# smart_irrigation.net
KiCad netlist of a schematic drawn in EAGLE
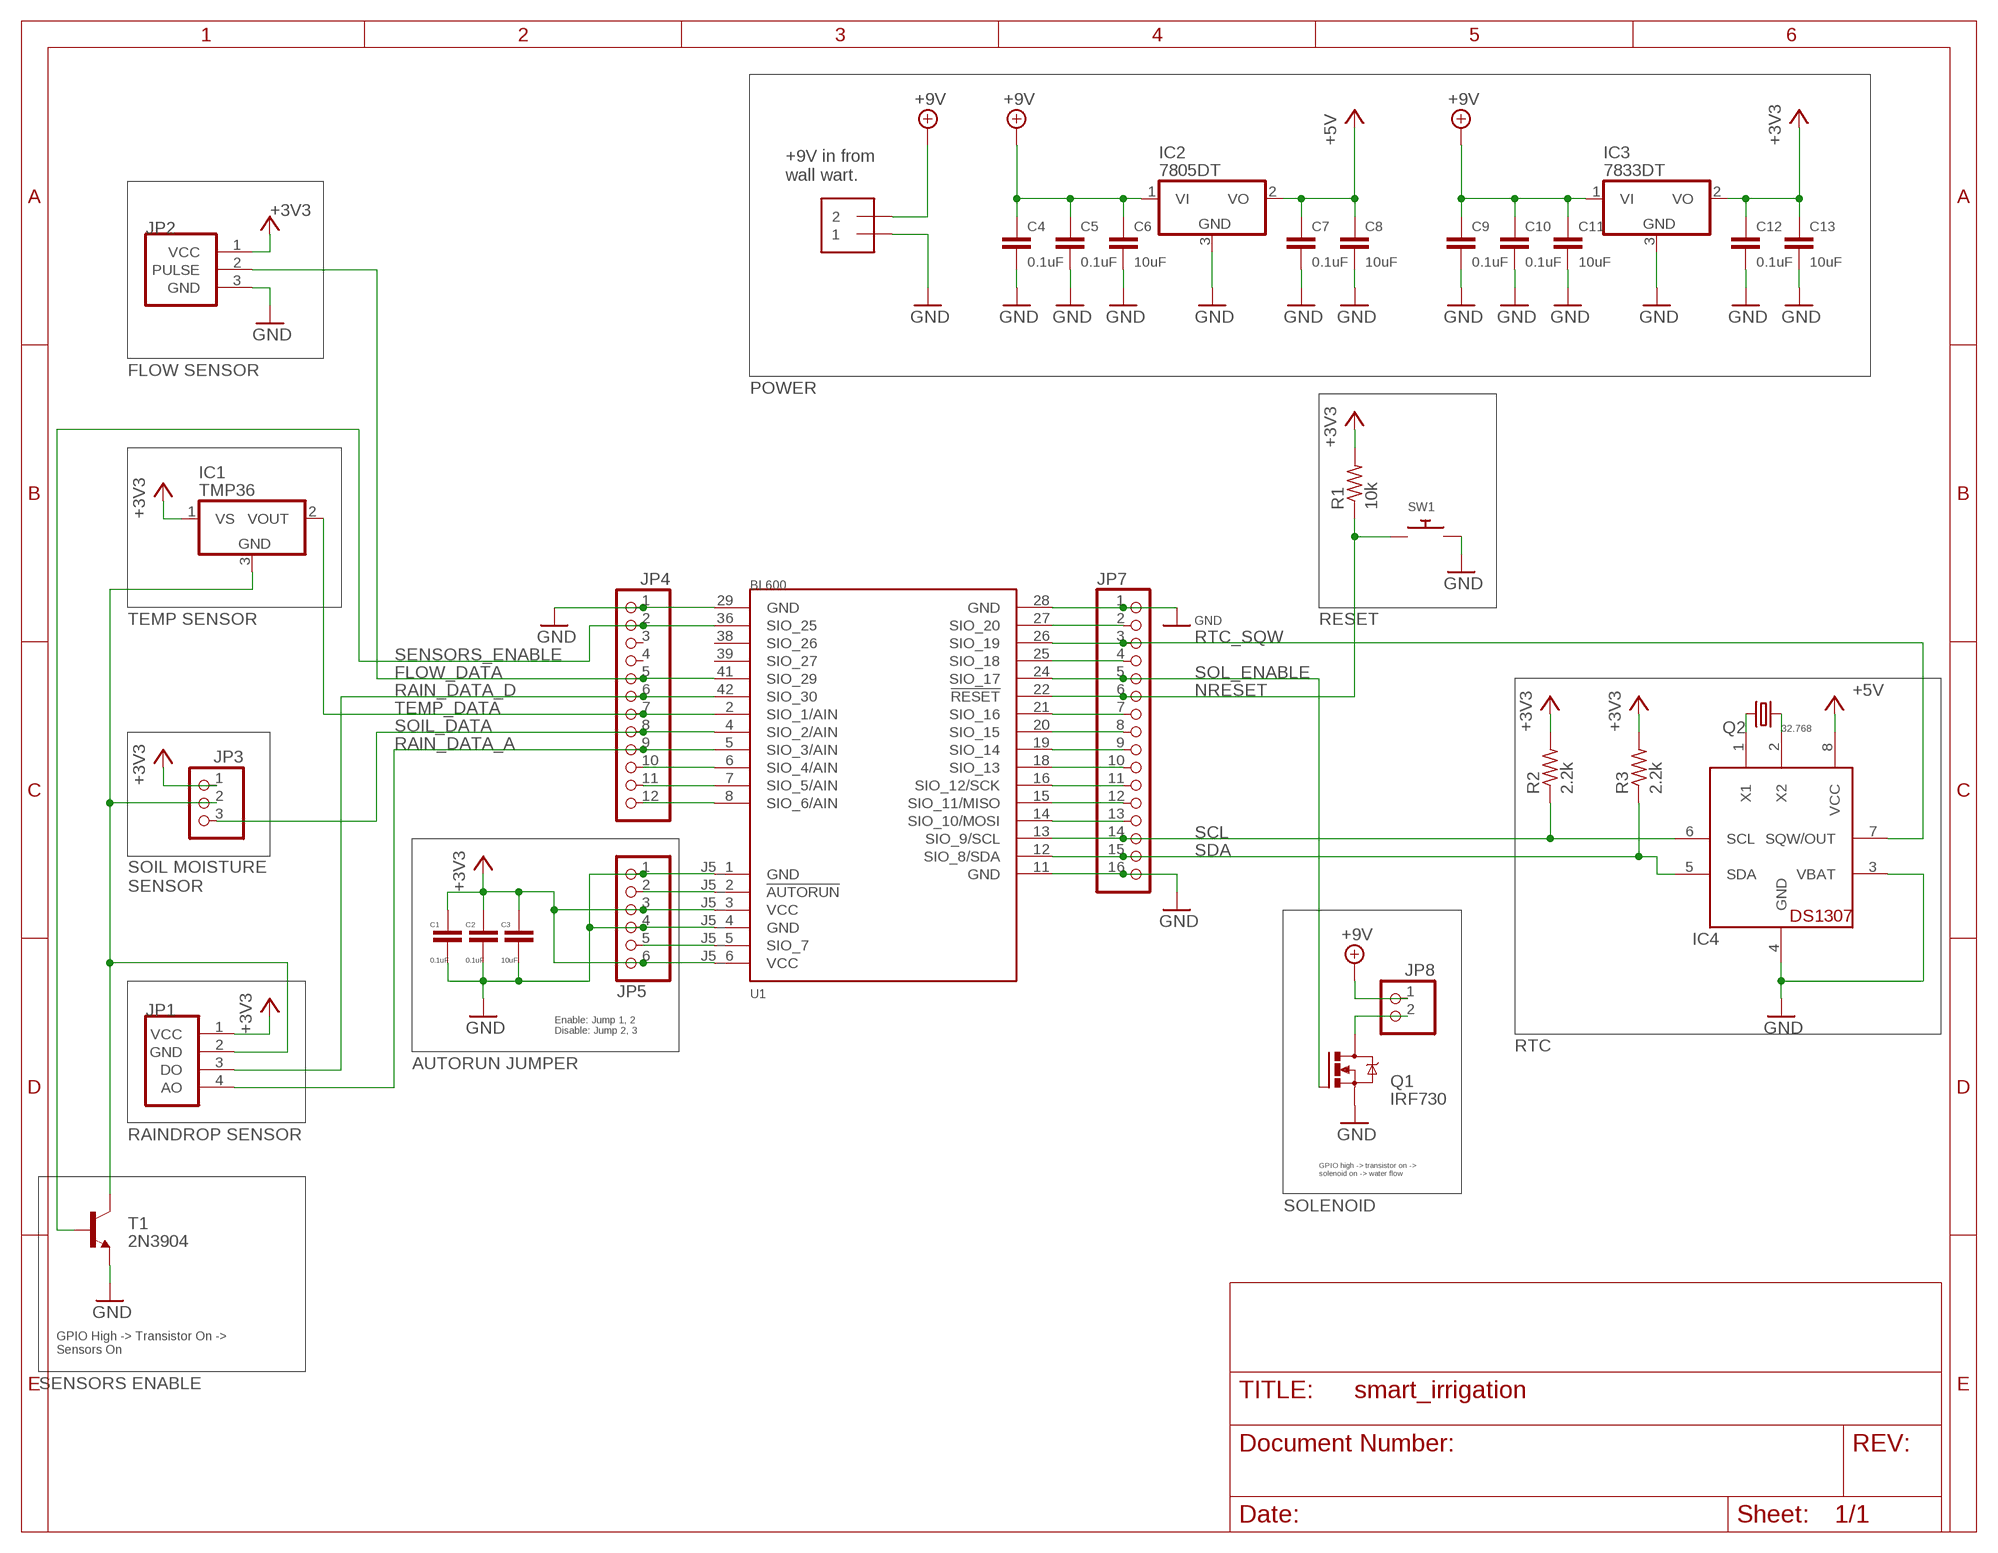
[diagram p0: schematic, sheet 1]

(export (version "E")
  (design (tool "Eeschema 10.0.6"))
  (components
    (comp (ref "C1")
      (value "0.1uF")
      (footprint "eagle-import:C0805")
      (libsource (lib "eagle-import") (part "C-EUC0805"))
    )
    (comp (ref "C2")
      (value "0.1uF")
      (footprint "eagle-import:C0805")
      (libsource (lib "eagle-import") (part "C-EUC0805"))
    )
    (comp (ref "C3")
      (value "10uF")
      (footprint "eagle-import:C0805")
      (libsource (lib "eagle-import") (part "C-EUC0805"))
    )
    (comp (ref "C4")
      (value "0.1uF")
      (footprint "eagle-import:C0805")
      (libsource (lib "eagle-import") (part "C-EUC0805"))
    )
    (comp (ref "C5")
      (value "0.1uF")
      (footprint "eagle-import:C0805")
      (libsource (lib "eagle-import") (part "C-EUC0805"))
    )
    (comp (ref "C6")
      (value "10uF")
      (footprint "eagle-import:C0805")
      (libsource (lib "eagle-import") (part "C-EUC0805"))
    )
    (comp (ref "C7")
      (value "0.1uF")
      (footprint "eagle-import:C0805")
      (libsource (lib "eagle-import") (part "C-EUC0805"))
    )
    (comp (ref "C8")
      (value "10uF")
      (footprint "eagle-import:C0805")
      (libsource (lib "eagle-import") (part "C-EUC0805"))
    )
    (comp (ref "C9")
      (value "0.1uF")
      (footprint "eagle-import:C0805")
      (libsource (lib "eagle-import") (part "C-EUC0805"))
    )
    (comp (ref "C10")
      (value "0.1uF")
      (footprint "eagle-import:C0805")
      (libsource (lib "eagle-import") (part "C-EUC0805"))
    )
    (comp (ref "C11")
      (value "10uF")
      (footprint "eagle-import:C0805")
      (libsource (lib "eagle-import") (part "C-EUC0805"))
    )
    (comp (ref "C12")
      (value "0.1uF")
      (footprint "eagle-import:C0805")
      (libsource (lib "eagle-import") (part "C-EUC0805"))
    )
    (comp (ref "C13")
      (value "10uF")
      (footprint "eagle-import:C0805")
      (libsource (lib "eagle-import") (part "C-EUC0805"))
    )
    (comp (ref "IC1")
      (value "TMP36")
      (footprint "eagle-import:TO92")
      (libsource (lib "eagle-import") (part "TMP36"))
    )
    (comp (ref "IC2")
      (value "7805DT")
      (footprint "eagle-import:TO252")
      (libsource (lib "eagle-import") (part "78DT05"))
    )
    (comp (ref "IC3")
      (value "7833DT")
      (footprint "eagle-import:TO252")
      (libsource (lib "eagle-import") (part "78DT33"))
    )
    (comp (ref "IC4")
      (value "DS1307")
      (footprint "eagle-import:DIL08")
      (libsource (lib "eagle-import") (part "DS1307"))
    )
    (comp (ref "JP1")
      (value "RAINDROP")
      (footprint "eagle-import:1X04")
      (libsource (lib "eagle-import") (part "RAINDROP"))
    )
    (comp (ref "JP2")
      (value "FLOW")
      (footprint "eagle-import:1X03")
      (libsource (lib "eagle-import") (part "FLOW"))
    )
    (comp (ref "JP3")
      (value "PINHD-1X3")
      (footprint "eagle-import:1X03")
      (libsource (lib "eagle-import") (part "PINHD-1X3"))
    )
    (comp (ref "JP4")
      (value "PINHD-1X12")
      (footprint "eagle-import:1X12")
      (libsource (lib "eagle-import") (part "PINHD-1X12"))
    )
    (comp (ref "JP5")
      (value "PINHD-1X6")
      (footprint "eagle-import:1X06")
      (libsource (lib "eagle-import") (part "PINHD-1X6"))
    )
    (comp (ref "JP6")
      (value "1X2-3.5MM")
      (footprint "eagle-import:1X2-3.5MM")
      (libsource (lib "eagle-import") (part "1X2-3.5MM"))
    )
    (comp (ref "JP7")
      (value "PINHD-1X16")
      (footprint "eagle-import:1X16")
      (libsource (lib "eagle-import") (part "PINHD-1X16"))
    )
    (comp (ref "JP8")
      (value "PINHD-1X2")
      (footprint "eagle-import:1X02")
      (libsource (lib "eagle-import") (part "PINHD-1X2"))
    )
    (comp (ref "Q1")
      (value "IRF730")
      (footprint "eagle-import:TO220")
      (libsource (lib "eagle-import") (part "IRF730"))
    )
    (comp (ref "Q2")
      (value "32.768")
      (footprint "eagle-import:TC38H")
      (libsource (lib "eagle-import") (part "CRYSTALTC38H"))
    )
    (comp (ref "R1")
      (value "10k")
      (footprint "eagle-import:M0805")
      (libsource (lib "eagle-import") (part "R-US_M0805"))
    )
    (comp (ref "R2")
      (value "2.2k")
      (footprint "eagle-import:M0805")
      (libsource (lib "eagle-import") (part "R-US_M0805"))
    )
    (comp (ref "R3")
      (value "2.2k")
      (footprint "eagle-import:M0805")
      (libsource (lib "eagle-import") (part "R-US_M0805"))
    )
    (comp (ref "SW1")
      (value "SWITCH_PUSHBUTTONEVQ-PE")
      (footprint "eagle-import:TACT_PANA-EVQ")
      (libsource (lib "eagle-import") (part "SWITCH_PUSHBUTTONEVQ-PE"))
    )
    (comp (ref "T1")
      (value "2N3904")
      (footprint "eagle-import:TO92")
      (libsource (lib "eagle-import") (part "2N3904"))
    )
    (comp (ref "U1")
      (value "BL600")
      (footprint "eagle-import:BOB")
      (libsource (lib "eagle-import") (part "BL600"))
    )
  )
  (nets
    (net (code "1") (name "+3V3") (class "Default")
      (node (ref "C1") (pin "1") (pinfunction "1_1") (pintype "passive"))
      (node (ref "C12") (pin "1") (pinfunction "1_1") (pintype "passive"))
      (node (ref "C13") (pin "1") (pinfunction "1_1") (pintype "passive"))
      (node (ref "C2") (pin "1") (pinfunction "1_1") (pintype "passive"))
      (node (ref "C3") (pin "1") (pinfunction "1_1") (pintype "passive"))
      (node (ref "IC1") (pin "1") (pinfunction "VS_1") (pintype "input"))
      (node (ref "IC3") (pin "2") (pinfunction "VO_2") (pintype "passive"))
      (node (ref "JP1") (pin "1") (pinfunction "VCC_1") (pintype "power_in"))
      (node (ref "JP2") (pin "1") (pinfunction "VCC_1") (pintype "power_in"))
      (node (ref "JP3") (pin "1") (pinfunction "1_1") (pintype "passive"))
      (node (ref "JP5") (pin "3") (pinfunction "3_3") (pintype "passive"))
      (node (ref "JP5") (pin "6") (pinfunction "6_6") (pintype "passive"))
      (node (ref "R1") (pin "2") (pinfunction "2_2") (pintype "passive"))
      (node (ref "R2") (pin "2") (pinfunction "2_2") (pintype "passive"))
      (node (ref "R3") (pin "2") (pinfunction "2_2") (pintype "passive"))
      (node (ref "U1") (pin "J5_3") (pinfunction "VCC_J5_3") (pintype "power_in"))
      (node (ref "U1") (pin "J5_6") (pinfunction "VCC_J5_6") (pintype "power_in"))
    )
    (net (code "2") (name "+5V") (class "Default")
      (node (ref "C7") (pin "1") (pinfunction "1_1") (pintype "passive"))
      (node (ref "C8") (pin "1") (pinfunction "1_1") (pintype "passive"))
      (node (ref "IC2") (pin "2") (pinfunction "VO_2") (pintype "passive"))
      (node (ref "IC4") (pin "8") (pinfunction "VCC_8") (pintype "power_in"))
    )
    (net (code "3") (name "+9V") (class "Default")
      (node (ref "C10") (pin "1") (pinfunction "1_1") (pintype "passive"))
      (node (ref "C11") (pin "1") (pinfunction "1_1") (pintype "passive"))
      (node (ref "C4") (pin "1") (pinfunction "1_1") (pintype "passive"))
      (node (ref "C5") (pin "1") (pinfunction "1_1") (pintype "passive"))
      (node (ref "C6") (pin "1") (pinfunction "1_1") (pintype "passive"))
      (node (ref "C9") (pin "1") (pinfunction "1_1") (pintype "passive"))
      (node (ref "IC2") (pin "1") (pinfunction "VI_1") (pintype "input"))
      (node (ref "IC3") (pin "1") (pinfunction "VI_1") (pintype "input"))
      (node (ref "JP6") (pin "2") (pinfunction "2_2") (pintype "passive"))
      (node (ref "JP8") (pin "1") (pinfunction "1_1") (pintype "passive"))
    )
    (net (code "4") (name "/FLOW_DATA") (class "Default")
      (node (ref "JP2") (pin "2") (pinfunction "PULSE_2") (pintype "output"))
      (node (ref "JP4") (pin "5") (pinfunction "5_5") (pintype "passive"))
      (node (ref "U1") (pin "41") (pinfunction "SIO_29_41") (pintype "bidirectional"))
    )
    (net (code "5") (name "/NRESET") (class "Default")
      (node (ref "JP7") (pin "6") (pinfunction "6_6") (pintype "passive"))
      (node (ref "R1") (pin "1") (pinfunction "1_1") (pintype "passive"))
      (node (ref "SW1") (pin "P$1") (pinfunction "P$1_P$1") (pintype "passive"))
      (node (ref "U1") (pin "22") (pinfunction "~{RESET}_22") (pintype "bidirectional"))
    )
    (net (code "6") (name "/RAIN_DATA_A") (class "Default")
      (node (ref "JP1") (pin "4") (pinfunction "AO_4") (pintype "output"))
      (node (ref "JP4") (pin "9") (pinfunction "9_9") (pintype "passive"))
      (node (ref "U1") (pin "5") (pinfunction "SIO_3/AIN_5") (pintype "bidirectional"))
    )
    (net (code "7") (name "/RAIN_DATA_D") (class "Default")
      (node (ref "JP1") (pin "3") (pinfunction "DO_3") (pintype "output"))
      (node (ref "JP4") (pin "6") (pinfunction "6_6") (pintype "passive"))
      (node (ref "U1") (pin "42") (pinfunction "SIO_30_42") (pintype "bidirectional"))
    )
    (net (code "8") (name "/RTC_SQW") (class "Default")
      (node (ref "IC4") (pin "7") (pinfunction "SQW/OUT_7") (pintype "bidirectional"))
      (node (ref "JP7") (pin "3") (pinfunction "3_3") (pintype "passive"))
      (node (ref "U1") (pin "26") (pinfunction "SIO_19_26") (pintype "bidirectional"))
    )
    (net (code "9") (name "/SCL") (class "Default")
      (node (ref "IC4") (pin "6") (pinfunction "SCL_6") (pintype "bidirectional"))
      (node (ref "JP7") (pin "14") (pinfunction "14_14") (pintype "passive"))
      (node (ref "R2") (pin "1") (pinfunction "1_1") (pintype "passive"))
      (node (ref "U1") (pin "13") (pinfunction "SIO_9/SCL_13") (pintype "bidirectional"))
    )
    (net (code "10") (name "/SDA") (class "Default")
      (node (ref "IC4") (pin "5") (pinfunction "SDA_5") (pintype "bidirectional"))
      (node (ref "JP7") (pin "15") (pinfunction "15_15") (pintype "passive"))
      (node (ref "R3") (pin "1") (pinfunction "1_1") (pintype "passive"))
      (node (ref "U1") (pin "12") (pinfunction "SIO_8/SDA_12") (pintype "bidirectional"))
    )
    (net (code "11") (name "/SENSORS_ENABLE") (class "Default")
      (node (ref "JP4") (pin "2") (pinfunction "2_2") (pintype "passive"))
      (node (ref "T1") (pin "2") (pinfunction "B_2") (pintype "passive"))
      (node (ref "U1") (pin "36") (pinfunction "SIO_25_36") (pintype "bidirectional"))
    )
    (net (code "12") (name "/SOIL_DATA") (class "Default")
      (node (ref "JP3") (pin "3") (pinfunction "3_3") (pintype "passive"))
      (node (ref "JP4") (pin "8") (pinfunction "8_8") (pintype "passive"))
      (node (ref "U1") (pin "4") (pinfunction "SIO_2/AIN_4") (pintype "bidirectional"))
    )
    (net (code "13") (name "/SOL_ENABLE") (class "Default")
      (node (ref "JP7") (pin "5") (pinfunction "5_5") (pintype "passive"))
      (node (ref "Q1") (pin "G") (pinfunction "G_G") (pintype "passive"))
      (node (ref "U1") (pin "24") (pinfunction "SIO_17_24") (pintype "bidirectional"))
    )
    (net (code "14") (name "/TEMP_DATA") (class "Default")
      (node (ref "IC1") (pin "2") (pinfunction "VOUT_2") (pintype "passive"))
      (node (ref "JP4") (pin "7") (pinfunction "7_7") (pintype "passive"))
      (node (ref "U1") (pin "2") (pinfunction "SIO_1/AIN_2") (pintype "bidirectional"))
    )
    (net (code "15") (name "GND") (class "Default")
      (node (ref "C1") (pin "2") (pinfunction "2_2") (pintype "passive"))
      (node (ref "C10") (pin "2") (pinfunction "2_2") (pintype "passive"))
      (node (ref "C11") (pin "2") (pinfunction "2_2") (pintype "passive"))
      (node (ref "C12") (pin "2") (pinfunction "2_2") (pintype "passive"))
      (node (ref "C13") (pin "2") (pinfunction "2_2") (pintype "passive"))
      (node (ref "C2") (pin "2") (pinfunction "2_2") (pintype "passive"))
      (node (ref "C3") (pin "2") (pinfunction "2_2") (pintype "passive"))
      (node (ref "C4") (pin "2") (pinfunction "2_2") (pintype "passive"))
      (node (ref "C5") (pin "2") (pinfunction "2_2") (pintype "passive"))
      (node (ref "C6") (pin "2") (pinfunction "2_2") (pintype "passive"))
      (node (ref "C7") (pin "2") (pinfunction "2_2") (pintype "passive"))
      (node (ref "C8") (pin "2") (pinfunction "2_2") (pintype "passive"))
      (node (ref "C9") (pin "2") (pinfunction "2_2") (pintype "passive"))
      (node (ref "IC2") (pin "3") (pinfunction "GND_3") (pintype "passive"))
      (node (ref "IC3") (pin "3") (pinfunction "GND_3") (pintype "passive"))
      (node (ref "IC4") (pin "3") (pinfunction "VBAT_3") (pintype "power_in"))
      (node (ref "IC4") (pin "4") (pinfunction "GND_4") (pintype "power_in"))
      (node (ref "JP2") (pin "3") (pinfunction "GND_3") (pintype "power_in"))
      (node (ref "JP4") (pin "1") (pinfunction "1_1") (pintype "passive"))
      (node (ref "JP5") (pin "1") (pinfunction "1_1") (pintype "passive"))
      (node (ref "JP5") (pin "4") (pinfunction "4_4") (pintype "passive"))
      (node (ref "JP6") (pin "1") (pinfunction "1_1") (pintype "passive"))
      (node (ref "JP7") (pin "1") (pinfunction "1_1") (pintype "passive"))
      (node (ref "JP7") (pin "16") (pinfunction "16_16") (pintype "passive"))
      (node (ref "Q1") (pin "S") (pinfunction "S_S") (pintype "passive"))
      (node (ref "SW1") (pin "P$2") (pinfunction "P$2_P$2") (pintype "passive"))
      (node (ref "T1") (pin "3") (pinfunction "E_3") (pintype "passive"))
      (node (ref "U1") (pin "11") (pinfunction "GND_11") (pintype "bidirectional"))
      (node (ref "U1") (pin "28") (pinfunction "GND_28") (pintype "bidirectional"))
      (node (ref "U1") (pin "29") (pinfunction "GND_29") (pintype "power_in"))
      (node (ref "U1") (pin "J5_1") (pinfunction "GND_J5_1") (pintype "power_in"))
      (node (ref "U1") (pin "J5_4") (pinfunction "GND_J5_4") (pintype "power_in"))
    )
    (net (code "16") (name "Net-(IC1-GND)") (class "Default")
      (node (ref "IC1") (pin "3") (pinfunction "GND_3") (pintype "passive"))
      (node (ref "JP1") (pin "2") (pinfunction "GND_2") (pintype "power_in"))
      (node (ref "JP3") (pin "2") (pinfunction "2_2") (pintype "passive"))
      (node (ref "T1") (pin "1") (pinfunction "C_1") (pintype "passive"))
    )
    (net (code "17") (name "Net-(IC4-X1)") (class "Default")
      (node (ref "IC4") (pin "1") (pinfunction "X1_1") (pintype "passive"))
      (node (ref "Q2") (pin "2") (pinfunction "2_2") (pintype "passive"))
    )
    (net (code "18") (name "Net-(IC4-X2)") (class "Default")
      (node (ref "IC4") (pin "2") (pinfunction "X2_2") (pintype "passive"))
      (node (ref "Q2") (pin "1") (pinfunction "1_1") (pintype "passive"))
    )
    (net (code "19") (name "Net-(JP8-Pad2)") (class "Default")
      (node (ref "JP8") (pin "2") (pinfunction "2_2") (pintype "passive"))
      (node (ref "Q1") (pin "D") (pinfunction "D_D") (pintype "passive"))
    )
    (net (code "20") (name "Net-(U1-SIO_4{slash}AIN)") (class "Default")
      (node (ref "JP4") (pin "10") (pinfunction "10_10") (pintype "passive"))
      (node (ref "U1") (pin "6") (pinfunction "SIO_4/AIN_6") (pintype "bidirectional"))
    )
    (net (code "21") (name "Net-(U1-SIO_5{slash}AIN)") (class "Default")
      (node (ref "JP4") (pin "11") (pinfunction "11_11") (pintype "passive"))
      (node (ref "U1") (pin "7") (pinfunction "SIO_5/AIN_7") (pintype "bidirectional"))
    )
    (net (code "22") (name "Net-(U1-SIO_6{slash}AIN)") (class "Default")
      (node (ref "JP4") (pin "12") (pinfunction "12_12") (pintype "passive"))
      (node (ref "U1") (pin "8") (pinfunction "SIO_6/AIN_8") (pintype "bidirectional"))
    )
    (net (code "23") (name "Net-(U1-SIO_7)") (class "Default")
      (node (ref "JP5") (pin "5") (pinfunction "5_5") (pintype "passive"))
      (node (ref "U1") (pin "J5_5") (pinfunction "SIO_7_J5_5") (pintype "bidirectional"))
    )
    (net (code "24") (name "Net-(U1-SIO_10{slash}MOSI)") (class "Default")
      (node (ref "JP7") (pin "13") (pinfunction "13_13") (pintype "passive"))
      (node (ref "U1") (pin "14") (pinfunction "SIO_10/MOSI_14") (pintype "bidirectional"))
    )
    (net (code "25") (name "Net-(U1-SIO_11{slash}MISO)") (class "Default")
      (node (ref "JP7") (pin "12") (pinfunction "12_12") (pintype "passive"))
      (node (ref "U1") (pin "15") (pinfunction "SIO_11/MISO_15") (pintype "bidirectional"))
    )
    (net (code "26") (name "Net-(U1-SIO_12{slash}SCK)") (class "Default")
      (node (ref "JP7") (pin "11") (pinfunction "11_11") (pintype "passive"))
      (node (ref "U1") (pin "16") (pinfunction "SIO_12/SCK_16") (pintype "bidirectional"))
    )
    (net (code "27") (name "Net-(U1-SIO_13)") (class "Default")
      (node (ref "JP7") (pin "10") (pinfunction "10_10") (pintype "passive"))
      (node (ref "U1") (pin "18") (pinfunction "SIO_13_18") (pintype "bidirectional"))
    )
    (net (code "28") (name "Net-(U1-SIO_14)") (class "Default")
      (node (ref "JP7") (pin "9") (pinfunction "9_9") (pintype "passive"))
      (node (ref "U1") (pin "19") (pinfunction "SIO_14_19") (pintype "bidirectional"))
    )
    (net (code "29") (name "Net-(U1-SIO_15)") (class "Default")
      (node (ref "JP7") (pin "8") (pinfunction "8_8") (pintype "passive"))
      (node (ref "U1") (pin "20") (pinfunction "SIO_15_20") (pintype "bidirectional"))
    )
    (net (code "30") (name "Net-(U1-SIO_16)") (class "Default")
      (node (ref "JP7") (pin "7") (pinfunction "7_7") (pintype "passive"))
      (node (ref "U1") (pin "21") (pinfunction "SIO_16_21") (pintype "bidirectional"))
    )
    (net (code "31") (name "Net-(U1-SIO_18)") (class "Default")
      (node (ref "JP7") (pin "4") (pinfunction "4_4") (pintype "passive"))
      (node (ref "U1") (pin "25") (pinfunction "SIO_18_25") (pintype "bidirectional"))
    )
    (net (code "32") (name "Net-(U1-SIO_20)") (class "Default")
      (node (ref "JP7") (pin "2") (pinfunction "2_2") (pintype "passive"))
      (node (ref "U1") (pin "27") (pinfunction "SIO_20_27") (pintype "bidirectional"))
    )
    (net (code "33") (name "Net-(U1-~{AUTORUN})") (class "Default")
      (node (ref "JP5") (pin "2") (pinfunction "2_2") (pintype "passive"))
      (node (ref "U1") (pin "J5_2") (pinfunction "~{AUTORUN}_J5_2") (pintype "bidirectional"))
    )
    (net (code "34") (name "unconnected-(JP4-Pad3)") (class "Default")
      (node (ref "JP4") (pin "3") (pinfunction "3_3") (pintype "passive"))
    )
    (net (code "35") (name "unconnected-(JP4-Pad4)") (class "Default")
      (node (ref "JP4") (pin "4") (pinfunction "4_4") (pintype "passive"))
    )
    (net (code "36") (name "unconnected-(U1-SIO_26-Pad38)") (class "Default")
      (node (ref "U1") (pin "38") (pinfunction "SIO_26_38") (pintype "bidirectional"))
    )
    (net (code "37") (name "unconnected-(U1-SIO_27-Pad39)") (class "Default")
      (node (ref "U1") (pin "39") (pinfunction "SIO_27_39") (pintype "bidirectional"))
    )
  )
)
